# warship_demo_2.net
KiCad netlist of a schematic drawn in Altium Designer
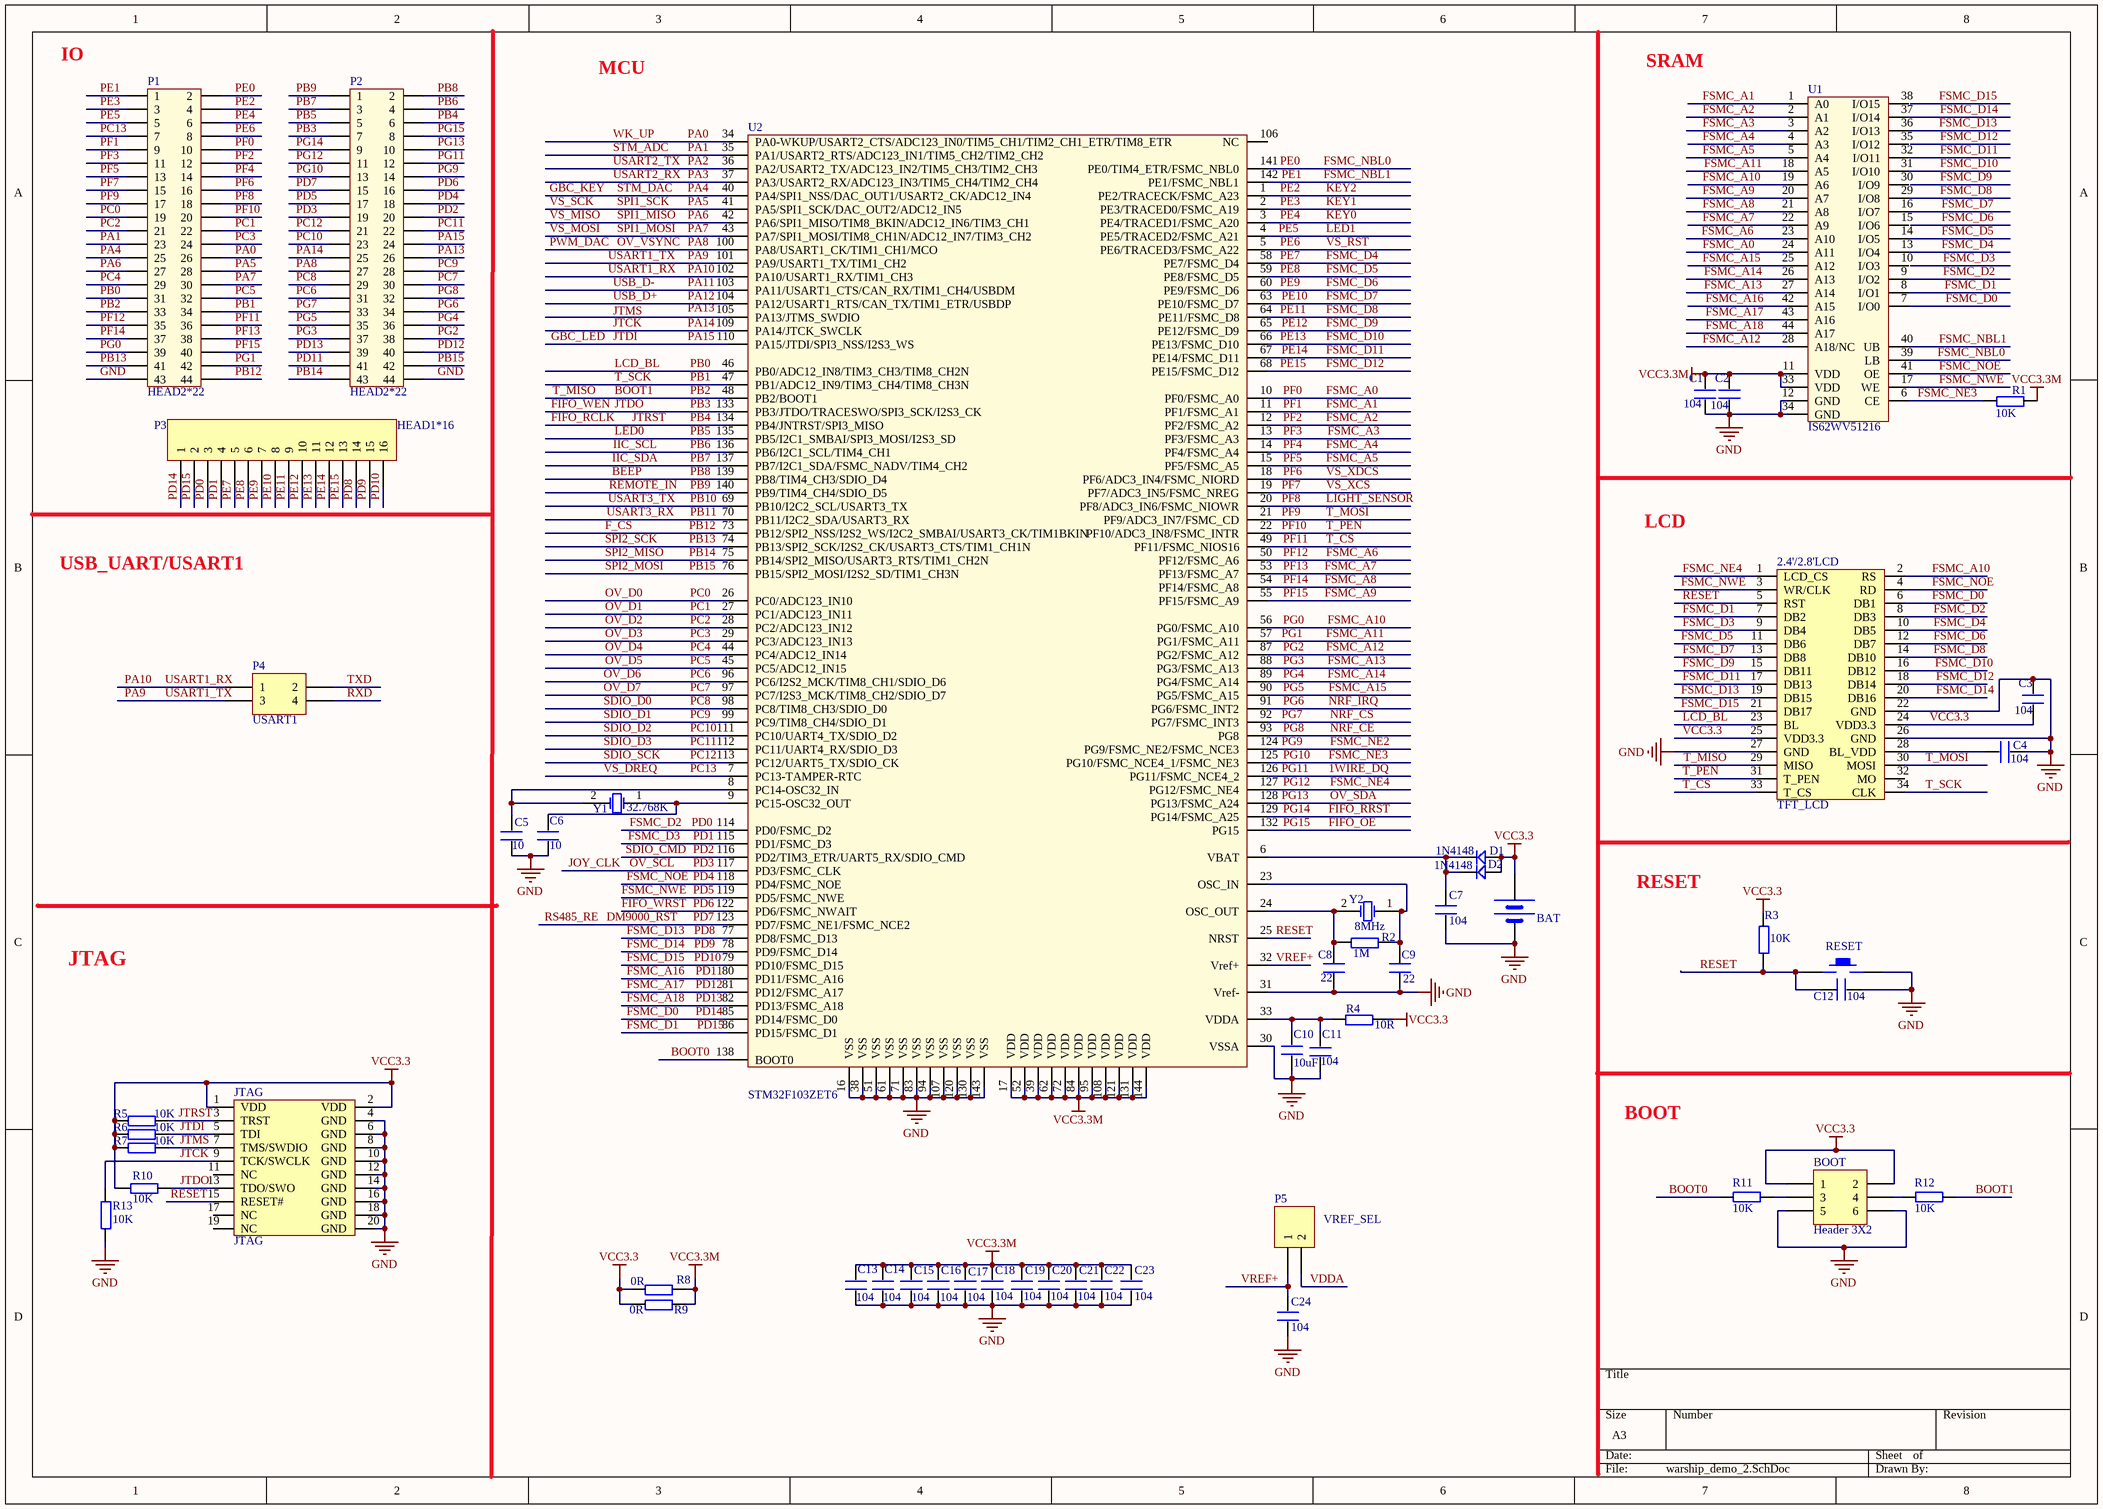
[diagram p0: warship_demo_2.SchDoc]

(export (version "E")
  (design (tool "Eeschema 10.0.6"))
  (components
    (comp (ref "2.4'/2.8'LCD")
      (value "TFT_LCD")
      (footprint "db2*17-4.3")
      (libsource (lib "WarShip V3 STM32103封装库") (part "TFT_LCD"))
    )
    (comp (ref "BAT")
      (value "BATT")
      (footprint "BATM")
      (libsource (lib "WarShip V3 STM32103封装库") (part "BAT"))
    )
    (comp (ref "BOOT")
      (value "Header 3X2")
      (footprint "HDR2X3")
      (description "Header, 3-Pin, Dual row")
      (fields (field (name "PUBLISHER") "Altium Limited"))
      (libsource (lib "WarShip V3 STM32103封装库") (part "Header 3X2"))
    )
    (comp (ref "C1") (value "104") (footprint "0603P") (libsource (lib "WarShip V3 STM32103封装库") (part "C")))
    (comp (ref "C2") (value "104") (footprint "0603P") (libsource (lib "WarShip V3 STM32103封装库") (part "C")))
    (comp (ref "C3") (value "104") (footprint "0603P") (libsource (lib "WarShip V3 STM32103封装库") (part "C")))
    (comp (ref "C4") (value "104") (footprint "0603P") (libsource (lib "WarShip V3 STM32103封装库") (part "C")))
    (comp (ref "C5") (value "10") (footprint "0603P") (libsource (lib "WarShip V3 STM32103封装库") (part "C")))
    (comp (ref "C6") (value "10") (footprint "0603P") (libsource (lib "WarShip V3 STM32103封装库") (part "C")))
    (comp (ref "C7") (value "104") (footprint "0603P") (libsource (lib "WarShip V3 STM32103封装库") (part "C")))
    (comp (ref "C8") (value "22") (footprint "0603P") (libsource (lib "WarShip V3 STM32103封装库") (part "C")))
    (comp (ref "C9") (value "22") (footprint "0603P") (libsource (lib "WarShip V3 STM32103封装库") (part "C")))
    (comp (ref "C10")
      (value "10uF")
      (footprint "0603P")
      (libsource (lib "WarShip V3 STM32103封装库") (part "C"))
    )
    (comp (ref "C11") (value "104") (footprint "0603P") (libsource (lib "WarShip V3 STM32103封装库") (part "C")))
    (comp (ref "C12") (value "104") (footprint "0603P") (libsource (lib "WarShip V3 STM32103封装库") (part "C")))
    (comp (ref "C13") (value "104") (footprint "0603P") (libsource (lib "WarShip V3 STM32103封装库") (part "C")))
    (comp (ref "C14") (value "104") (footprint "0603P") (libsource (lib "WarShip V3 STM32103封装库") (part "C")))
    (comp (ref "C15") (value "104") (footprint "0603P") (libsource (lib "WarShip V3 STM32103封装库") (part "C")))
    (comp (ref "C16") (value "104") (footprint "0603P") (libsource (lib "WarShip V3 STM32103封装库") (part "C")))
    (comp (ref "C17") (value "104") (footprint "0603P") (libsource (lib "WarShip V3 STM32103封装库") (part "C")))
    (comp (ref "C18") (value "104") (footprint "0603P") (libsource (lib "WarShip V3 STM32103封装库") (part "C")))
    (comp (ref "C19") (value "104") (footprint "0603P") (libsource (lib "WarShip V3 STM32103封装库") (part "C")))
    (comp (ref "C20") (value "104") (footprint "0603P") (libsource (lib "WarShip V3 STM32103封装库") (part "C")))
    (comp (ref "C21") (value "104") (footprint "0603P") (libsource (lib "WarShip V3 STM32103封装库") (part "C")))
    (comp (ref "C22") (value "104") (footprint "0603P") (libsource (lib "WarShip V3 STM32103封装库") (part "C")))
    (comp (ref "C23") (value "104") (footprint "0603P") (libsource (lib "WarShip V3 STM32103封装库") (part "C")))
    (comp (ref "C24") (value "104") (footprint "0603P") (libsource (lib "WarShip V3 STM32103封装库") (part "C")))
    (comp (ref "D1")
      (value "1N4148")
      (footprint "DIODE_SOP")
      (libsource (lib "WarShip V3 STM32103封装库") (part "D"))
    )
    (comp (ref "D2")
      (value "1N4148")
      (footprint "DIODE_SOP")
      (libsource (lib "WarShip V3 STM32103封装库") (part "D"))
    )
    (comp (ref "JTAG")
      (value "JTAG")
      (footprint "JTAG_20")
      (libsource (lib "WarShip V3 STM32103封装库") (part "JTAG"))
    )
    (comp (ref "P1")
      (value "HEAD2*22")
      (footprint "HEAD2*22")
      (libsource (lib "WarShip V3 STM32103封装库") (part "HEAD2*22"))
    )
    (comp (ref "P2")
      (value "HEAD2*22")
      (footprint "HEAD2*22")
      (libsource (lib "WarShip V3 STM32103封装库") (part "HEAD2*22"))
    )
    (comp (ref "P3")
      (value "HEAD1*16")
      (footprint "HDR1X16")
      (description "Header, 16-Pin")
      (fields (field (name "PUBLISHER") "Altium Limited"))
      (libsource (lib "WarShip V3 STM32103封装库") (part "Header 16"))
    )
    (comp (ref "P4")
      (value "USART1")
      (footprint "HDR2X2")
      (description "Header, 2-Pin, Dual row")
      (fields (field (name "PUBLISHER") "Altium Limited"))
      (libsource (lib "WarShip V3 STM32103封装库") (part "Header 2X2"))
    )
    (comp (ref "P5")
      (value "VREF_SEL")
      (footprint "HDR1X2")
      (description "Header, 2-Pin")
      (fields (field (name "PUBLISHER") "Altium Limited"))
      (libsource (lib "WarShip V3 STM32103封装库") (part "Header 2"))
    )
    (comp (ref "R1") (value "10K") (footprint "0603P") (libsource (lib "WarShip V3 STM32103封装库") (part "R")))
    (comp (ref "R2") (value "1M") (footprint "0603P") (libsource (lib "WarShip V3 STM32103封装库") (part "R")))
    (comp (ref "R3") (value "10K") (footprint "0603P") (libsource (lib "WarShip V3 STM32103封装库") (part "R")))
    (comp (ref "R4") (value "10R") (footprint "0603P") (libsource (lib "WarShip V3 STM32103封装库") (part "R")))
    (comp (ref "R5") (value "10K") (footprint "0603P") (libsource (lib "WarShip V3 STM32103封装库") (part "R")))
    (comp (ref "R6") (value "10K") (footprint "0603P") (libsource (lib "WarShip V3 STM32103封装库") (part "R")))
    (comp (ref "R7") (value "10K") (footprint "0603P") (libsource (lib "WarShip V3 STM32103封装库") (part "R")))
    (comp (ref "R8") (value "0R") (footprint "0603P") (libsource (lib "WarShip V3 STM32103封装库") (part "R")))
    (comp (ref "R9") (value "0R") (footprint "0603P") (libsource (lib "WarShip V3 STM32103封装库") (part "R")))
    (comp (ref "R10") (value "10K") (footprint "0603P") (libsource (lib "WarShip V3 STM32103封装库") (part "R")))
    (comp (ref "R11") (value "10K") (footprint "0603P") (libsource (lib "WarShip V3 STM32103封装库") (part "R")))
    (comp (ref "R12") (value "10K") (footprint "0603P") (libsource (lib "WarShip V3 STM32103封装库") (part "R")))
    (comp (ref "R13") (value "10K") (footprint "0603P") (libsource (lib "WarShip V3 STM32103封装库") (part "R")))
    (comp (ref "RESET")
      (value "KEY_M")
      (footprint "KEY_M")
      (libsource (lib "WarShip V3 STM32103封装库") (part "KEY_M"))
    )
    (comp (ref "U1")
      (value "IS62WV51216")
      (footprint "TSOP44")
      (libsource (lib "WarShip V3 STM32103封装库") (part "IS61LV51216"))
    )
    (comp (ref "U2")
      (value "STM32F103ZET6")
      (footprint "LQFP144")
      (libsource (lib "WarShip V3 STM32103封装库") (part "STM32F103ZET6"))
    )
    (comp (ref "Y1")
      (value "32.768K")
      (footprint "XTAL_US")
      (description "Crystal Oscillator")
      (fields (field (name "PUBLISHER") "Altium Limited"))
      (libsource (lib "WarShip V3 STM32103封装库") (part "XTAL"))
    )
    (comp (ref "Y2")
      (value "8MHz")
      (footprint "XTAL_US")
      (description "Crystal Oscillator")
      (fields (field (name "PUBLISHER") "Altium Limited"))
      (libsource (lib "WarShip V3 STM32103封装库") (part "XTAL"))
    )
  )
  (nets
    (net (code "1") (name "/1WIRE_DQ") (class "Default")
      (node (ref "P2") (pin "12") (pinfunction "12_12") (pintype "passive"))
      (node (ref "U2") (pin "126") (pinfunction "PG11/FSMC_NCE4_2_126") (pintype "passive"))
    )
    (net (code "2") (name "/BEEP") (class "Default")
      (node (ref "P2") (pin "2") (pinfunction "2_2") (pintype "passive"))
      (node (ref "U2") (pin "139") (pinfunction "PB8/TIM4_CH3/SDIO_D4_139") (pintype "passive"))
    )
    (net (code "3") (name "/BOOT0") (class "Default")
      (node (ref "R11") (pin "2") (pintype "passive"))
      (node (ref "U2") (pin "138") (pinfunction "BOOT0_138") (pintype "passive"))
    )
    (net (code "4") (name "/BOOT1") (class "Default")
      (node (ref "2.4'/2.8'LCD") (pin "29") (pinfunction "MISO_29") (pintype "passive"))
      (node (ref "P1") (pin "33") (pinfunction "33_33") (pintype "passive"))
      (node (ref "R12") (pin "1") (pintype "passive"))
      (node (ref "U2") (pin "48") (pinfunction "PB2/BOOT1_48") (pintype "passive"))
    )
    (net (code "5") (name "/DM9000_RST") (class "Default")
      (node (ref "P2") (pin "15") (pinfunction "15_15") (pintype "passive"))
      (node (ref "U2") (pin "123") (pinfunction "PD7/FSMC_NE1/FSMC_NCE2_123") (pintype "passive"))
    )
    (net (code "6") (name "/FIFO_OE") (class "Default")
      (node (ref "P2") (pin "8") (pinfunction "8_8") (pintype "passive"))
      (node (ref "U2") (pin "132") (pinfunction "PG15_132") (pintype "passive"))
    )
    (net (code "7") (name "/FIFO_RCLK") (class "Default")
      (node (ref "JTAG") (pin "3") (pinfunction "TRST_3") (pintype "passive"))
      (node (ref "P2") (pin "6") (pinfunction "6_6") (pintype "passive"))
      (node (ref "R5") (pin "2") (pintype "passive"))
      (node (ref "U2") (pin "134") (pinfunction "PB4/JNTRST/SPI3_MISO_134") (pintype "passive"))
    )
    (net (code "8") (name "/FIFO_RRST") (class "Default")
      (node (ref "P2") (pin "9") (pinfunction "9_9") (pintype "passive"))
      (node (ref "U2") (pin "129") (pinfunction "PG14/FSMC_A25_129") (pintype "passive"))
    )
    (net (code "9") (name "/FIFO_WEN") (class "Default")
      (node (ref "JTAG") (pin "13") (pinfunction "TDO/SWO_13") (pintype "passive"))
      (node (ref "P2") (pin "7") (pinfunction "7_7") (pintype "passive"))
      (node (ref "R10") (pin "2") (pintype "passive"))
      (node (ref "U2") (pin "133") (pinfunction "PB3/JTDO/TRACESWO/SPI3_SCK/I2S3_CK_133") (pintype "passive"))
    )
    (net (code "10") (name "/FIFO_WRST") (class "Default")
      (node (ref "P2") (pin "16") (pinfunction "16_16") (pintype "passive"))
      (node (ref "U2") (pin "122") (pinfunction "PD6/FSMC_NWAIT_122") (pintype "passive"))
    )
    (net (code "11") (name "/FSMC_A0") (class "Default")
      (node (ref "P1") (pin "10") (pinfunction "10_10") (pintype "passive"))
      (node (ref "U1") (pin "24") (pinfunction "A11_24") (pintype "passive"))
      (node (ref "U2") (pin "10") (pinfunction "PF0/FSMC_A0_10") (pintype "passive"))
    )
    (net (code "12") (name "/FSMC_A1") (class "Default")
      (node (ref "P1") (pin "9") (pinfunction "9_9") (pintype "passive"))
      (node (ref "U1") (pin "1") (pinfunction "A0_1") (pintype "passive"))
      (node (ref "U2") (pin "11") (pinfunction "PF1/FSMC_A1_11") (pintype "passive"))
    )
    (net (code "13") (name "/FSMC_A2") (class "Default")
      (node (ref "P1") (pin "12") (pinfunction "12_12") (pintype "passive"))
      (node (ref "U1") (pin "2") (pinfunction "A1_2") (pintype "passive"))
      (node (ref "U2") (pin "12") (pinfunction "PF2/FSMC_A2_12") (pintype "passive"))
    )
    (net (code "14") (name "/FSMC_A3") (class "Default")
      (node (ref "P1") (pin "11") (pinfunction "11_11") (pintype "passive"))
      (node (ref "U1") (pin "3") (pinfunction "A2_3") (pintype "passive"))
      (node (ref "U2") (pin "13") (pinfunction "PF3/FSMC_A3_13") (pintype "passive"))
    )
    (net (code "15") (name "/FSMC_A4") (class "Default")
      (node (ref "P1") (pin "14") (pinfunction "14_14") (pintype "passive"))
      (node (ref "U1") (pin "4") (pinfunction "A3_4") (pintype "passive"))
      (node (ref "U2") (pin "14") (pinfunction "PF4/FSMC_A4_14") (pintype "passive"))
    )
    (net (code "16") (name "/FSMC_A5") (class "Default")
      (node (ref "P1") (pin "13") (pinfunction "13_13") (pintype "passive"))
      (node (ref "U1") (pin "5") (pinfunction "A4_5") (pintype "passive"))
      (node (ref "U2") (pin "15") (pinfunction "PF5/FSMC_A5_15") (pintype "passive"))
    )
    (net (code "17") (name "/FSMC_A6") (class "Default")
      (node (ref "P1") (pin "35") (pinfunction "35_35") (pintype "passive"))
      (node (ref "U1") (pin "23") (pinfunction "A10_23") (pintype "passive"))
      (node (ref "U2") (pin "50") (pinfunction "PF12/FSMC_A6_50") (pintype "passive"))
    )
    (net (code "18") (name "/FSMC_A7") (class "Default")
      (node (ref "P1") (pin "38") (pinfunction "38_38") (pintype "passive"))
      (node (ref "U1") (pin "22") (pinfunction "A9_22") (pintype "passive"))
      (node (ref "U2") (pin "53") (pinfunction "PF13/FSMC_A7_53") (pintype "passive"))
    )
    (net (code "19") (name "/FSMC_A8") (class "Default")
      (node (ref "P1") (pin "37") (pinfunction "37_37") (pintype "passive"))
      (node (ref "U1") (pin "21") (pinfunction "A8_21") (pintype "passive"))
      (node (ref "U2") (pin "54") (pinfunction "PF14/FSMC_A8_54") (pintype "passive"))
    )
    (net (code "20") (name "/FSMC_A9") (class "Default")
      (node (ref "P1") (pin "40") (pinfunction "40_40") (pintype "passive"))
      (node (ref "U1") (pin "20") (pinfunction "A7_20") (pintype "passive"))
      (node (ref "U2") (pin "55") (pinfunction "PF15/FSMC_A9_55") (pintype "passive"))
    )
    (net (code "21") (name "/FSMC_A10") (class "Default")
      (node (ref "2.4'/2.8'LCD") (pin "2") (pinfunction "RS_2") (pintype "passive"))
      (node (ref "P1") (pin "39") (pinfunction "39_39") (pintype "passive"))
      (node (ref "U1") (pin "19") (pinfunction "A6_19") (pintype "passive"))
      (node (ref "U2") (pin "56") (pinfunction "PG0/FSMC_A10_56") (pintype "passive"))
    )
    (net (code "22") (name "/FSMC_A11") (class "Default")
      (node (ref "P1") (pin "42") (pinfunction "42_42") (pintype "passive"))
      (node (ref "U1") (pin "18") (pinfunction "A5_18") (pintype "passive"))
      (node (ref "U2") (pin "57") (pinfunction "PG1/FSMC_A11_57") (pintype "passive"))
    )
    (net (code "23") (name "/FSMC_A12") (class "Default")
      (node (ref "P2") (pin "38") (pinfunction "38_38") (pintype "passive"))
      (node (ref "U1") (pin "28") (pinfunction "A18/NC_28") (pintype "passive"))
      (node (ref "U2") (pin "87") (pinfunction "PG2/FSMC_A12_87") (pintype "passive"))
    )
    (net (code "24") (name "/FSMC_A13") (class "Default")
      (node (ref "P2") (pin "37") (pinfunction "37_37") (pintype "passive"))
      (node (ref "U1") (pin "27") (pinfunction "A14_27") (pintype "passive"))
      (node (ref "U2") (pin "88") (pinfunction "PG3/FSMC_A13_88") (pintype "passive"))
    )
    (net (code "25") (name "/FSMC_A14") (class "Default")
      (node (ref "P2") (pin "36") (pinfunction "36_36") (pintype "passive"))
      (node (ref "U1") (pin "26") (pinfunction "A13_26") (pintype "passive"))
      (node (ref "U2") (pin "89") (pinfunction "PG4/FSMC_A14_89") (pintype "passive"))
    )
    (net (code "26") (name "/FSMC_A15") (class "Default")
      (node (ref "P2") (pin "35") (pinfunction "35_35") (pintype "passive"))
      (node (ref "U1") (pin "25") (pinfunction "A12_25") (pintype "passive"))
      (node (ref "U2") (pin "90") (pinfunction "PG5/FSMC_A15_90") (pintype "passive"))
    )
    (net (code "27") (name "/FSMC_A16") (class "Default")
      (node (ref "P2") (pin "41") (pinfunction "41_41") (pintype "passive"))
      (node (ref "U1") (pin "42") (pinfunction "A15_42") (pintype "passive"))
      (node (ref "U2") (pin "80") (pinfunction "PD11/FSMC_A16_80") (pintype "passive"))
    )
    (net (code "28") (name "/FSMC_A17") (class "Default")
      (node (ref "P2") (pin "40") (pinfunction "40_40") (pintype "passive"))
      (node (ref "U1") (pin "43") (pinfunction "A16_43") (pintype "passive"))
      (node (ref "U2") (pin "81") (pinfunction "PD12/FSMC_A17_81") (pintype "passive"))
    )
    (net (code "29") (name "/FSMC_A18") (class "Default")
      (node (ref "P2") (pin "39") (pinfunction "39_39") (pintype "passive"))
      (node (ref "U1") (pin "44") (pinfunction "A17_44") (pintype "passive"))
      (node (ref "U2") (pin "82") (pinfunction "PD13/FSMC_A18_82") (pintype "passive"))
    )
    (net (code "30") (name "/FSMC_D0") (class "Default")
      (node (ref "2.4'/2.8'LCD") (pin "6") (pinfunction "DB1_6") (pintype "passive"))
      (node (ref "P3") (pin "1") (pinfunction "1_1") (pintype "passive"))
      (node (ref "U1") (pin "7") (pinfunction "I/O0_7") (pintype "passive"))
      (node (ref "U2") (pin "85") (pinfunction "PD14/FSMC_D0_85") (pintype "passive"))
    )
    (net (code "31") (name "/FSMC_D1") (class "Default")
      (node (ref "2.4'/2.8'LCD") (pin "7") (pinfunction "DB2_7") (pintype "passive"))
      (node (ref "P3") (pin "2") (pinfunction "2_2") (pintype "passive"))
      (node (ref "U1") (pin "8") (pinfunction "I/O1_8") (pintype "passive"))
      (node (ref "U2") (pin "86") (pinfunction "PD15/FSMC_D1_86") (pintype "passive"))
    )
    (net (code "32") (name "/FSMC_D2") (class "Default")
      (node (ref "2.4'/2.8'LCD") (pin "8") (pinfunction "DB3_8") (pintype "passive"))
      (node (ref "P3") (pin "3") (pinfunction "3_3") (pintype "passive"))
      (node (ref "U1") (pin "9") (pinfunction "I/O2_9") (pintype "passive"))
      (node (ref "U2") (pin "114") (pinfunction "PD0/FSMC_D2_114") (pintype "passive"))
    )
    (net (code "33") (name "/FSMC_D3") (class "Default")
      (node (ref "2.4'/2.8'LCD") (pin "9") (pinfunction "DB4_9") (pintype "passive"))
      (node (ref "P3") (pin "4") (pinfunction "4_4") (pintype "passive"))
      (node (ref "U2") (pin "115") (pinfunction "PD1/FSMC_D3_115") (pintype "passive"))
    )
    (net (code "34") (name "/FSMC_D4") (class "Default")
      (node (ref "2.4'/2.8'LCD") (pin "10") (pinfunction "DB5_10") (pintype "passive"))
      (node (ref "P3") (pin "5") (pinfunction "5_5") (pintype "passive"))
      (node (ref "U1") (pin "13") (pinfunction "I/O4_13") (pintype "passive"))
      (node (ref "U2") (pin "58") (pinfunction "PE7/FSMC_D4_58") (pintype "passive"))
    )
    (net (code "35") (name "/FSMC_D5") (class "Default")
      (node (ref "2.4'/2.8'LCD") (pin "11") (pinfunction "DB6_11") (pintype "passive"))
      (node (ref "P3") (pin "6") (pinfunction "6_6") (pintype "passive"))
      (node (ref "U1") (pin "14") (pinfunction "I/O5_14") (pintype "passive"))
      (node (ref "U2") (pin "59") (pinfunction "PE8/FSMC_D5_59") (pintype "passive"))
    )
    (net (code "36") (name "/FSMC_D6") (class "Default")
      (node (ref "2.4'/2.8'LCD") (pin "12") (pinfunction "DB7_12") (pintype "passive"))
      (node (ref "P3") (pin "7") (pinfunction "7_7") (pintype "passive"))
      (node (ref "U2") (pin "60") (pinfunction "PE9/FSMC_D6_60") (pintype "passive"))
    )
    (net (code "37") (name "/FSMC_D7") (class "Default")
      (node (ref "2.4'/2.8'LCD") (pin "13") (pinfunction "DB8_13") (pintype "passive"))
      (node (ref "P3") (pin "8") (pinfunction "8_8") (pintype "passive"))
      (node (ref "U1") (pin "16") (pinfunction "I/O7_16") (pintype "passive"))
      (node (ref "U2") (pin "63") (pinfunction "PE10/FSMC_D7_63") (pintype "passive"))
    )
    (net (code "38") (name "/FSMC_D8") (class "Default")
      (node (ref "2.4'/2.8'LCD") (pin "14") (pinfunction "DB10_14") (pintype "passive"))
      (node (ref "P3") (pin "9") (pinfunction "9_9") (pintype "passive"))
      (node (ref "U1") (pin "29") (pinfunction "I/O8_29") (pintype "passive"))
      (node (ref "U2") (pin "64") (pinfunction "PE11/FSMC_D8_64") (pintype "passive"))
    )
    (net (code "39") (name "/FSMC_D9") (class "Default")
      (node (ref "2.4'/2.8'LCD") (pin "15") (pinfunction "DB11_15") (pintype "passive"))
      (node (ref "P3") (pin "10") (pinfunction "10_10") (pintype "passive"))
      (node (ref "U2") (pin "65") (pinfunction "PE12/FSMC_D9_65") (pintype "passive"))
    )
    (net (code "40") (name "/FSMC_D10") (class "Default")
      (node (ref "2.4'/2.8'LCD") (pin "16") (pinfunction "DB12_16") (pintype "passive"))
      (node (ref "P3") (pin "11") (pinfunction "11_11") (pintype "passive"))
      (node (ref "U1") (pin "31") (pinfunction "I/O10_31") (pintype "passive"))
      (node (ref "U2") (pin "66") (pinfunction "PE13/FSMC_D10_66") (pintype "passive"))
    )
    (net (code "41") (name "/FSMC_D11") (class "Default")
      (node (ref "2.4'/2.8'LCD") (pin "17") (pinfunction "DB13_17") (pintype "passive"))
      (node (ref "P3") (pin "12") (pinfunction "12_12") (pintype "passive"))
      (node (ref "U1") (pin "32") (pinfunction "I/O11_32") (pintype "passive"))
      (node (ref "U2") (pin "67") (pinfunction "PE14/FSMC_D11_67") (pintype "passive"))
    )
    (net (code "42") (name "/FSMC_D12") (class "Default")
      (node (ref "2.4'/2.8'LCD") (pin "18") (pinfunction "DB14_18") (pintype "passive"))
      (node (ref "P3") (pin "13") (pinfunction "13_13") (pintype "passive"))
      (node (ref "U2") (pin "68") (pinfunction "PE15/FSMC_D12_68") (pintype "passive"))
    )
    (net (code "43") (name "/FSMC_D13") (class "Default")
      (node (ref "2.4'/2.8'LCD") (pin "19") (pinfunction "DB15_19") (pintype "passive"))
      (node (ref "P3") (pin "14") (pinfunction "14_14") (pintype "passive"))
      (node (ref "U1") (pin "36") (pinfunction "I/O13_36") (pintype "passive"))
      (node (ref "U2") (pin "77") (pinfunction "PD8/FSMC_D13_77") (pintype "passive"))
    )
    (net (code "44") (name "/FSMC_D14") (class "Default")
      (node (ref "2.4'/2.8'LCD") (pin "20") (pinfunction "DB16_20") (pintype "passive"))
      (node (ref "P3") (pin "15") (pinfunction "15_15") (pintype "passive"))
      (node (ref "U1") (pin "37") (pinfunction "I/O14_37") (pintype "passive"))
      (node (ref "U2") (pin "78") (pinfunction "PD9/FSMC_D14_78") (pintype "passive"))
    )
    (net (code "45") (name "/FSMC_D15") (class "Default")
      (node (ref "2.4'/2.8'LCD") (pin "21") (pinfunction "DB17_21") (pintype "passive"))
      (node (ref "P3") (pin "16") (pinfunction "16_16") (pintype "passive"))
      (node (ref "U2") (pin "79") (pinfunction "PD10/FSMC_D15_79") (pintype "passive"))
    )
    (net (code "46") (name "/FSMC_NBL0") (class "Default")
      (node (ref "P1") (pin "2") (pinfunction "2_2") (pintype "passive"))
      (node (ref "U1") (pin "39") (pinfunction "LB_39") (pintype "passive"))
      (node (ref "U2") (pin "141") (pinfunction "PE0/TIM4_ETR/FSMC_NBL0_141") (pintype "passive"))
    )
    (net (code "47") (name "/FSMC_NBL1") (class "Default")
      (node (ref "P1") (pin "1") (pinfunction "1_1") (pintype "passive"))
      (node (ref "U1") (pin "40") (pinfunction "UB_40") (pintype "passive"))
      (node (ref "U2") (pin "142") (pinfunction "PE1/FSMC_NBL1_142") (pintype "passive"))
    )
    (net (code "48") (name "/FSMC_NE2") (class "Default")
      (node (ref "P2") (pin "14") (pinfunction "14_14") (pintype "passive"))
      (node (ref "U2") (pin "124") (pinfunction "PG9/FSMC_NE2/FSMC_NCE3_124") (pintype "passive"))
    )
    (net (code "49") (name "/FSMC_NE3") (class "Default")
      (node (ref "P2") (pin "13") (pinfunction "13_13") (pintype "passive"))
      (node (ref "R1") (pin "1") (pintype "passive"))
      (node (ref "U1") (pin "6") (pinfunction "CE_6") (pintype "passive"))
      (node (ref "U2") (pin "125") (pinfunction "PG10/FSMC_NCE4_1/FSMC_NE3_125") (pintype "passive"))
    )
    (net (code "50") (name "/FSMC_NE4") (class "Default")
      (node (ref "2.4'/2.8'LCD") (pin "1") (pinfunction "LCD_CS_1") (pintype "passive"))
      (node (ref "P2") (pin "11") (pinfunction "11_11") (pintype "passive"))
      (node (ref "U2") (pin "127") (pinfunction "PG12/FSMC_NE4_127") (pintype "passive"))
    )
    (net (code "51") (name "/FSMC_NOE") (class "Default")
      (node (ref "2.4'/2.8'LCD") (pin "4") (pinfunction "RD_4") (pintype "passive"))
      (node (ref "P2") (pin "18") (pinfunction "18_18") (pintype "passive"))
      (node (ref "U1") (pin "41") (pinfunction "OE_41") (pintype "passive"))
      (node (ref "U2") (pin "118") (pinfunction "PD4/FSMC_NOE_118") (pintype "passive"))
    )
    (net (code "52") (name "/FSMC_NWE") (class "Default")
      (node (ref "2.4'/2.8'LCD") (pin "3") (pinfunction "WR/CLK_3") (pintype "passive"))
      (node (ref "P2") (pin "17") (pinfunction "17_17") (pintype "passive"))
      (node (ref "U1") (pin "17") (pinfunction "WE_17") (pintype "passive"))
      (node (ref "U2") (pin "119") (pinfunction "PD5/FSMC_NWE_119") (pintype "passive"))
    )
    (net (code "53") (name "/F_CS") (class "Default")
      (node (ref "P1") (pin "44") (pinfunction "44_44") (pintype "passive"))
      (node (ref "U2") (pin "73") (pinfunction "PB12/SPI2_NSS/I2S2_WS/I2C2_SMBAI/USART3_CK/TIM1BKIN_73") (pintype "passive"))
    )
    (net (code "54") (name "/GBC_KEY") (class "Default")
      (node (ref "P1") (pin "25") (pinfunction "25_25") (pintype "passive"))
      (node (ref "U2") (pin "40") (pinfunction "PA4/SPI1_NSS/DAC_OUT1/USART2_CK/ADC12_IN4_40") (pintype "passive"))
    )
    (net (code "55") (name "/GBC_LED") (class "Default")
      (node (ref "JTAG") (pin "5") (pinfunction "TDI_5") (pintype "passive"))
      (node (ref "P2") (pin "24") (pinfunction "24_24") (pintype "passive"))
      (node (ref "R6") (pin "2") (pintype "passive"))
      (node (ref "U2") (pin "110") (pinfunction "PA15/JTDI/SPI3_NSS/I2S3_WS_110") (pintype "passive"))
    )
    (net (code "56") (name "/IIC_SCL") (class "Default")
      (node (ref "P2") (pin "4") (pinfunction "4_4") (pintype "passive"))
      (node (ref "U2") (pin "136") (pinfunction "PB6/I2C1_SCL/TIM4_CH1_136") (pintype "passive"))
    )
    (net (code "57") (name "/IIC_SDA") (class "Default")
      (node (ref "P2") (pin "3") (pinfunction "3_3") (pintype "passive"))
      (node (ref "U2") (pin "137") (pinfunction "PB7/I2C1_SDA/FSMC_NADV/TIM4_CH2_137") (pintype "passive"))
    )
    (net (code "58") (name "/JOY_CLK") (class "Default")
      (node (ref "P2") (pin "19") (pinfunction "19_19") (pintype "passive"))
      (node (ref "U2") (pin "117") (pinfunction "PD3/FSMC_CLK_117") (pintype "passive"))
    )
    (net (code "59") (name "/JTCK") (class "Default")
      (node (ref "JTAG") (pin "9") (pinfunction "TCK/SWCLK_9") (pintype "passive"))
      (node (ref "P2") (pin "25") (pinfunction "25_25") (pintype "passive"))
      (node (ref "R13") (pin "2") (pintype "passive"))
      (node (ref "U2") (pin "109") (pinfunction "PA14/JTCK_SWCLK_109") (pintype "passive"))
    )
    (net (code "60") (name "/JTMS") (class "Default")
      (node (ref "JTAG") (pin "7") (pinfunction "TMS/SWDIO_7") (pintype "passive"))
      (node (ref "R7") (pin "2") (pintype "passive"))
    )
    (net (code "61") (name "/KEY0") (class "Default")
      (node (ref "P1") (pin "6") (pinfunction "6_6") (pintype "passive"))
      (node (ref "U2") (pin "3") (pinfunction "PE4/TRACED1/FSMC_A20_3") (pintype "passive"))
    )
    (net (code "62") (name "/KEY1") (class "Default")
      (node (ref "P1") (pin "3") (pinfunction "3_3") (pintype "passive"))
      (node (ref "U2") (pin "2") (pinfunction "PE3/TRACED0/FSMC_A19_2") (pintype "passive"))
    )
    (net (code "63") (name "/KEY2") (class "Default")
      (node (ref "P1") (pin "4") (pinfunction "4_4") (pintype "passive"))
      (node (ref "U2") (pin "1") (pinfunction "PE2/TRACECK/FSMC_A23_1") (pintype "passive"))
    )
    (net (code "64") (name "/LCD_BL") (class "Default")
      (node (ref "2.4'/2.8'LCD") (pin "23") (pinfunction "BL_23") (pintype "passive"))
      (node (ref "P1") (pin "31") (pinfunction "31_31") (pintype "passive"))
      (node (ref "U2") (pin "46") (pinfunction "PB0/ADC12_IN8/TIM3_CH3/TIM8_CH2N_46") (pintype "passive"))
    )
    (net (code "65") (name "/LED0") (class "Default")
      (node (ref "P2") (pin "5") (pinfunction "5_5") (pintype "passive"))
      (node (ref "U2") (pin "135") (pinfunction "PB5/I2C1_SMBAI/SPI3_MOSI/I2S3_SD_135") (pintype "passive"))
    )
    (net (code "66") (name "/LED1") (class "Default")
      (node (ref "P1") (pin "5") (pinfunction "5_5") (pintype "passive"))
      (node (ref "U2") (pin "4") (pinfunction "PE5/TRACED2/FSMC_A21_4") (pintype "passive"))
    )
    (net (code "67") (name "/LIGHT_SENSOR") (class "Default")
      (node (ref "P1") (pin "18") (pinfunction "18_18") (pintype "passive"))
      (node (ref "U2") (pin "20") (pinfunction "PF8/ADC3_IN6/FSMC_NIOWR_20") (pintype "passive"))
    )
    (net (code "68") (name "/NRF_CE") (class "Default")
      (node (ref "P2") (pin "32") (pinfunction "32_32") (pintype "passive"))
      (node (ref "U2") (pin "93") (pinfunction "PG8_93") (pintype "passive"))
    )
    (net (code "69") (name "/NRF_CS") (class "Default")
      (node (ref "P2") (pin "33") (pinfunction "33_33") (pintype "passive"))
      (node (ref "U2") (pin "92") (pinfunction "PG7/FSMC_INT3_92") (pintype "passive"))
    )
    (net (code "70") (name "/NRF_IRQ") (class "Default")
      (node (ref "P2") (pin "34") (pinfunction "34_34") (pintype "passive"))
      (node (ref "U2") (pin "91") (pinfunction "PG6/FSMC_INT2_91") (pintype "passive"))
    )
    (net (code "71") (name "/OV_D0") (class "Default")
      (node (ref "P1") (pin "19") (pinfunction "19_19") (pintype "passive"))
      (node (ref "U2") (pin "26") (pinfunction "PC0/ADC123_IN10_26") (pintype "passive"))
    )
    (net (code "72") (name "/OV_D1") (class "Default")
      (node (ref "P1") (pin "22") (pinfunction "22_22") (pintype "passive"))
      (node (ref "U2") (pin "27") (pinfunction "PC1/ADC123_IN11_27") (pintype "passive"))
    )
    (net (code "73") (name "/OV_D2") (class "Default")
      (node (ref "P1") (pin "21") (pinfunction "21_21") (pintype "passive"))
      (node (ref "U2") (pin "28") (pinfunction "PC2/ADC123_IN12_28") (pintype "passive"))
    )
    (net (code "74") (name "/OV_D3") (class "Default")
      (node (ref "P1") (pin "24") (pinfunction "24_24") (pintype "passive"))
      (node (ref "U2") (pin "29") (pinfunction "PC3/ADC123_IN13_29") (pintype "passive"))
    )
    (net (code "75") (name "/OV_D4") (class "Default")
      (node (ref "P1") (pin "29") (pinfunction "29_29") (pintype "passive"))
      (node (ref "U2") (pin "44") (pinfunction "PC4/ADC12_IN14_44") (pintype "passive"))
    )
    (net (code "76") (name "/OV_D5") (class "Default")
      (node (ref "P1") (pin "32") (pinfunction "32_32") (pintype "passive"))
      (node (ref "U2") (pin "45") (pinfunction "PC5/ADC12_IN15_45") (pintype "passive"))
    )
    (net (code "77") (name "/OV_D6") (class "Default")
      (node (ref "P2") (pin "31") (pinfunction "31_31") (pintype "passive"))
      (node (ref "U2") (pin "96") (pinfunction "PC6/I2S2_MCK/TIM8_CH1/SDIO_D6_96") (pintype "passive"))
    )
    (net (code "78") (name "/OV_D7") (class "Default")
      (node (ref "P2") (pin "30") (pinfunction "30_30") (pintype "passive"))
      (node (ref "U2") (pin "97") (pinfunction "PC7/I2S3_MCK/TIM8_CH2/SDIO_D7_97") (pintype "passive"))
    )
    (net (code "79") (name "/OV_SDA") (class "Default")
      (node (ref "P2") (pin "10") (pinfunction "10_10") (pintype "passive"))
      (node (ref "U2") (pin "128") (pinfunction "PG13/FSMC_A24_128") (pintype "passive"))
    )
    (net (code "80") (name "/OV_VSYNC") (class "Default")
      (node (ref "P2") (pin "27") (pinfunction "27_27") (pintype "passive"))
      (node (ref "U2") (pin "100") (pinfunction "PA8/USART1_CK/TIM1_CH1/MCO_100") (pintype "passive"))
    )
    (net (code "81") (name "/PA0") (class "Default")
      (node (ref "P1") (pin "26") (pinfunction "26_26") (pintype "passive"))
      (node (ref "U2") (pin "34") (pinfunction "PA0-WKUP/USART2_CTS/ADC123_IN0/TIM5_CH1/TIM2_CH1_ETR/TIM8_ETR_34") (pintype "passive"))
    )
    (net (code "82") (name "/PA1") (class "Default")
      (node (ref "P1") (pin "23") (pinfunction "23_23") (pintype "passive"))
      (node (ref "U2") (pin "35") (pinfunction "PA1/USART2_RTS/ADC123_IN1/TIM5_CH2/TIM2_CH2_35") (pintype "passive"))
    )
    (net (code "83") (name "/PA2") (class "Default")
      (node (ref "U2") (pin "36") (pinfunction "PA2/USART2_TX/ADC123_IN2/TIM5_CH3/TIM2_CH3_36") (pintype "passive"))
    )
    (net (code "84") (name "/PA3") (class "Default")
      (node (ref "U2") (pin "37") (pinfunction "PA3/USART2_RX/ADC123_IN3/TIM5_CH4/TIM2_CH4_37") (pintype "passive"))
    )
    (net (code "85") (name "/PA5") (class "Default")
      (node (ref "P1") (pin "28") (pinfunction "28_28") (pintype "passive"))
      (node (ref "U2") (pin "41") (pinfunction "PA5/SPI1_SCK/DAC_OUT2/ADC12_IN5_41") (pintype "passive"))
    )
    (net (code "86") (name "/PA6") (class "Default")
      (node (ref "P1") (pin "27") (pinfunction "27_27") (pintype "passive"))
      (node (ref "U2") (pin "42") (pinfunction "PA6/SPI1_MISO/TIM8_BKIN/ADC12_IN6/TIM3_CH1_42") (pintype "passive"))
    )
    (net (code "87") (name "/PA7") (class "Default")
      (node (ref "P1") (pin "30") (pinfunction "30_30") (pintype "passive"))
      (node (ref "U2") (pin "43") (pinfunction "PA7/SPI1_MOSI/TIM8_CH1N/ADC12_IN7/TIM3_CH2_43") (pintype "passive"))
    )
    (net (code "88") (name "/PA9") (class "Default")
      (node (ref "P4") (pin "3") (pinfunction "3_3") (pintype "passive"))
      (node (ref "U2") (pin "101") (pinfunction "PA9/USART1_TX/TIM1_CH2_101") (pintype "passive"))
    )
    (net (code "89") (name "/PA10") (class "Default")
      (node (ref "P4") (pin "1") (pinfunction "1_1") (pintype "passive"))
      (node (ref "U2") (pin "102") (pinfunction "PA10/USART1_RX/TIM1_CH3_102") (pintype "passive"))
    )
    (net (code "90") (name "/PA11") (class "Default")
      (node (ref "U2") (pin "103") (pinfunction "PA11/USART1_CTS/CAN_RX/TIM1_CH4/USBDM_103") (pintype "passive"))
    )
    (net (code "91") (name "/PA12") (class "Default")
      (node (ref "U2") (pin "104") (pinfunction "PA12/USART1_RTS/CAN_TX/TIM1_ETR/USBDP_104") (pintype "passive"))
    )
    (net (code "92") (name "/PA13") (class "Default")
      (node (ref "P2") (pin "26") (pinfunction "26_26") (pintype "passive"))
    )
    (net (code "93") (name "/PB1") (class "Default")
      (node (ref "2.4'/2.8'LCD") (pin "34") (pinfunction "CLK_34") (pintype "passive"))
      (node (ref "P1") (pin "34") (pinfunction "34_34") (pintype "passive"))
      (node (ref "U2") (pin "47") (pinfunction "PB1/ADC12_IN9/TIM3_CH4/TIM8_CH3N_47") (pintype "passive"))
    )
    (net (code "94") (name "/PB9") (class "Default")
      (node (ref "P2") (pin "1") (pinfunction "1_1") (pintype "passive"))
      (node (ref "U2") (pin "140") (pinfunction "PB9/TIM4_CH4/SDIO_D5_140") (pintype "passive"))
    )
    (net (code "95") (name "/PB10") (class "Default")
      (node (ref "U2") (pin "69") (pinfunction "PB10/I2C2_SCL/USART3_TX_69") (pintype "passive"))
    )
    (net (code "96") (name "/PB11") (class "Default")
      (node (ref "U2") (pin "70") (pinfunction "PB11/I2C2_SDA/USART3_RX_70") (pintype "passive"))
    )
    (net (code "97") (name "/PB13") (class "Default")
      (node (ref "P1") (pin "41") (pinfunction "41_41") (pintype "passive"))
      (node (ref "U2") (pin "74") (pinfunction "PB13/SPI2_SCK/I2S2_CK/USART3_CTS/TIM1_CH1N_74") (pintype "passive"))
    )
    (net (code "98") (name "/PB14") (class "Default")
      (node (ref "P2") (pin "43") (pinfunction "43_43") (pintype "passive"))
      (node (ref "U2") (pin "75") (pinfunction "PB14/SPI2_MISO/USART3_RTS/TIM1_CH2N_75") (pintype "passive"))
    )
    (net (code "99") (name "/PB15") (class "Default")
      (node (ref "P2") (pin "42") (pinfunction "42_42") (pintype "passive"))
      (node (ref "U2") (pin "76") (pinfunction "PB15/SPI2_MOSI/I2S2_SD/TIM1_CH3N_76") (pintype "passive"))
    )
    (net (code "100") (name "/PC8") (class "Default")
      (node (ref "P2") (pin "29") (pinfunction "29_29") (pintype "passive"))
      (node (ref "U2") (pin "98") (pinfunction "PC8/TIM8_CH3/SDIO_D0_98") (pintype "passive"))
    )
    (net (code "101") (name "/PC9") (class "Default")
      (node (ref "P2") (pin "28") (pinfunction "28_28") (pintype "passive"))
      (node (ref "U2") (pin "99") (pinfunction "PC9/TIM8_CH4/SDIO_D1_99") (pintype "passive"))
    )
    (net (code "102") (name "/PC10") (class "Default")
      (node (ref "P2") (pin "23") (pinfunction "23_23") (pintype "passive"))
      (node (ref "U2") (pin "111") (pinfunction "PC10/UART4_TX/SDIO_D2_111") (pintype "passive"))
    )
    (net (code "103") (name "/PC11") (class "Default")
      (node (ref "P2") (pin "22") (pinfunction "22_22") (pintype "passive"))
      (node (ref "U2") (pin "112") (pinfunction "PC11/UART4_RX/SDIO_D3_112") (pintype "passive"))
    )
    (net (code "104") (name "/PC12") (class "Default")
      (node (ref "P2") (pin "21") (pinfunction "21_21") (pintype "passive"))
      (node (ref "U2") (pin "113") (pinfunction "PC12/UART5_TX/SDIO_CK_113") (pintype "passive"))
    )
    (net (code "105") (name "/PC13") (class "Default")
      (node (ref "P1") (pin "7") (pinfunction "7_7") (pintype "passive"))
      (node (ref "U2") (pin "7") (pinfunction "PC13-TAMPER-RTC_7") (pintype "passive"))
    )
    (net (code "106") (name "/PD2") (class "Default")
      (node (ref "P2") (pin "20") (pinfunction "20_20") (pintype "passive"))
      (node (ref "U2") (pin "116") (pinfunction "PD2/TIM3_ETR/UART5_RX/SDIO_CMD_116") (pintype "passive"))
    )
    (net (code "107") (name "/PE6") (class "Default")
      (node (ref "P1") (pin "8") (pinfunction "8_8") (pintype "passive"))
      (node (ref "U2") (pin "5") (pinfunction "PE6/TRACED3/FSMC_A22_5") (pintype "passive"))
    )
    (net (code "108") (name "/PF6") (class "Default")
      (node (ref "P1") (pin "16") (pinfunction "16_16") (pintype "passive"))
      (node (ref "U2") (pin "18") (pinfunction "PF6/ADC3_IN4/FSMC_NIORD_18") (pintype "passive"))
    )
    (net (code "109") (name "/PF7") (class "Default")
      (node (ref "P1") (pin "15") (pinfunction "15_15") (pintype "passive"))
      (node (ref "U2") (pin "19") (pinfunction "PF7/ADC3_IN5/FSMC_NREG_19") (pintype "passive"))
    )
    (net (code "110") (name "/PF9") (class "Default")
      (node (ref "2.4'/2.8'LCD") (pin "30") (pinfunction "MOSI_30") (pintype "passive"))
      (node (ref "P1") (pin "17") (pinfunction "17_17") (pintype "passive"))
      (node (ref "U2") (pin "21") (pinfunction "PF9/ADC3_IN7/FSMC_CD_21") (pintype "passive"))
    )
    (net (code "111") (name "/PF10") (class "Default")
      (node (ref "2.4'/2.8'LCD") (pin "31") (pinfunction "T_PEN_31") (pintype "passive"))
      (node (ref "P1") (pin "20") (pinfunction "20_20") (pintype "passive"))
      (node (ref "U2") (pin "22") (pinfunction "PF10/ADC3_IN8/FSMC_INTR_22") (pintype "passive"))
    )
    (net (code "112") (name "/PF11") (class "Default")
      (node (ref "2.4'/2.8'LCD") (pin "33") (pinfunction "T_CS_33") (pintype "passive"))
      (node (ref "P1") (pin "36") (pinfunction "36_36") (pintype "passive"))
      (node (ref "U2") (pin "49") (pinfunction "PF11/FSMC_NIOS16_49") (pintype "passive"))
    )
    (net (code "113") (name "/RESET") (class "Default")
      (node (ref "2.4'/2.8'LCD") (pin "5") (pinfunction "RST_5") (pintype "passive"))
      (node (ref "C12") (pin "1") (pintype "passive"))
      (node (ref "JTAG") (pin "15") (pinfunction "RESET#_15") (pintype "passive"))
      (node (ref "R3") (pin "1") (pintype "passive"))
      (node (ref "RESET") (pin "1") (pinfunction "1_1") (pintype "passive"))
      (node (ref "U2") (pin "25") (pinfunction "NRST_25") (pintype "passive"))
    )
    (net (code "114") (name "/RXD") (class "Default")
      (node (ref "P4") (pin "4") (pinfunction "4_4") (pintype "passive"))
    )
    (net (code "115") (name "/TXD") (class "Default")
      (node (ref "P4") (pin "2") (pinfunction "2_2") (pintype "passive"))
    )
    (net (code "116") (name "/VDDA") (class "Default")
      (node (ref "P5") (pin "2") (pinfunction "2_2") (pintype "passive"))
    )
    (net (code "117") (name "/VREF+") (class "Default")
      (node (ref "C24") (pin "2") (pintype "passive"))
      (node (ref "P5") (pin "1") (pinfunction "1_1") (pintype "passive"))
      (node (ref "U2") (pin "32") (pinfunction "Vref+_32") (pintype "passive"))
    )
    (net (code "118") (name "GND") (class "Default")
      (node (ref "2.4'/2.8'LCD") (pin "22") (pinfunction "GND_22") (pintype "passive"))
      (node (ref "2.4'/2.8'LCD") (pin "26") (pinfunction "GND_26") (pintype "passive"))
      (node (ref "2.4'/2.8'LCD") (pin "27") (pinfunction "GND_27") (pintype "passive"))
      (node (ref "BAT") (pin "2") (pinfunction "GND_2") (pintype "passive"))
      (node (ref "BOOT") (pin "5") (pinfunction "5_5") (pintype "passive"))
      (node (ref "BOOT") (pin "6") (pinfunction "6_6") (pintype "passive"))
      (node (ref "C1") (pin "1") (pintype "passive"))
      (node (ref "C10") (pin "1") (pintype "passive"))
      (node (ref "C11") (pin "2") (pintype "passive"))
      (node (ref "C12") (pin "2") (pintype "passive"))
      (node (ref "C13") (pin "1") (pintype "passive"))
      (node (ref "C14") (pin "1") (pintype "passive"))
      (node (ref "C15") (pin "1") (pintype "passive"))
      (node (ref "C16") (pin "1") (pintype "passive"))
      (node (ref "C17") (pin "1") (pintype "passive"))
      (node (ref "C18") (pin "1") (pintype "passive"))
      (node (ref "C19") (pin "1") (pintype "passive"))
      (node (ref "C2") (pin "2") (pintype "passive"))
      (node (ref "C20") (pin "1") (pintype "passive"))
      (node (ref "C21") (pin "1") (pintype "passive"))
      (node (ref "C22") (pin "1") (pintype "passive"))
      (node (ref "C23") (pin "1") (pintype "passive"))
      (node (ref "C24") (pin "1") (pintype "passive"))
      (node (ref "C3") (pin "1") (pintype "passive"))
      (node (ref "C4") (pin "2") (pintype "passive"))
      (node (ref "C5") (pin "1") (pintype "passive"))
      (node (ref "C6") (pin "1") (pintype "passive"))
      (node (ref "C7") (pin "1") (pintype "passive"))
      (node (ref "C8") (pin "1") (pintype "passive"))
      (node (ref "C9") (pin "2") (pintype "passive"))
      (node (ref "JTAG") (pin "10") (pinfunction "GND_10") (pintype "passive"))
      (node (ref "JTAG") (pin "12") (pinfunction "GND_12") (pintype "passive"))
      (node (ref "JTAG") (pin "14") (pinfunction "GND_14") (pintype "passive"))
      (node (ref "JTAG") (pin "16") (pinfunction "GND_16") (pintype "passive"))
      (node (ref "JTAG") (pin "18") (pinfunction "GND_18") (pintype "passive"))
      (node (ref "JTAG") (pin "20") (pinfunction "GND_20") (pintype "passive"))
      (node (ref "JTAG") (pin "4") (pinfunction "GND_4") (pintype "passive"))
      (node (ref "JTAG") (pin "6") (pinfunction "GND_6") (pintype "passive"))
      (node (ref "JTAG") (pin "8") (pinfunction "GND_8") (pintype "passive"))
      (node (ref "P1") (pin "43") (pinfunction "43_43") (pintype "passive"))
      (node (ref "P2") (pin "44") (pinfunction "44_44") (pintype "passive"))
      (node (ref "R13") (pin "1") (pintype "passive"))
      (node (ref "RESET") (pin "2") (pinfunction "2_2") (pintype "passive"))
      (node (ref "U1") (pin "12") (pinfunction "GND_12") (pintype "passive"))
      (node (ref "U1") (pin "34") (pinfunction "GND_34") (pintype "passive"))
      (node (ref "U2") (pin "107") (pinfunction "VSS_107") (pintype "passive"))
      (node (ref "U2") (pin "120") (pinfunction "VSS_120") (pintype "passive"))
      (node (ref "U2") (pin "130") (pinfunction "VSS_130") (pintype "passive"))
      (node (ref "U2") (pin "143") (pinfunction "VSS_143") (pintype "passive"))
      (node (ref "U2") (pin "16") (pinfunction "VSS_16") (pintype "passive"))
      (node (ref "U2") (pin "30") (pinfunction "VSSA_30") (pintype "passive"))
      (node (ref "U2") (pin "31") (pinfunction "Vref-_31") (pintype "passive"))
      (node (ref "U2") (pin "38") (pinfunction "VSS_38") (pintype "passive"))
      (node (ref "U2") (pin "51") (pinfunction "VSS_51") (pintype "passive"))
      (node (ref "U2") (pin "61") (pinfunction "VSS_61") (pintype "passive"))
      (node (ref "U2") (pin "71") (pinfunction "VSS_71") (pintype "passive"))
      (node (ref "U2") (pin "83") (pinfunction "VSS_83") (pintype "passive"))
      (node (ref "U2") (pin "94") (pinfunction "VSS_94") (pintype "passive"))
    )
    (net (code "119") (name "Net-(2.4'/2.8'LCD-BL_VDD)") (class "Default")
      (node (ref "2.4'/2.8'LCD") (pin "28") (pinfunction "BL_VDD_28") (pintype "passive"))
      (node (ref "C4") (pin "1") (pintype "passive"))
    )
    (net (code "120") (name "Net-(BOOT-Pad3)") (class "Default")
      (node (ref "BOOT") (pin "3") (pinfunction "3_3") (pintype "passive"))
      (node (ref "R11") (pin "1") (pintype "passive"))
    )
    (net (code "121") (name "Net-(BOOT-Pad4)") (class "Default")
      (node (ref "BOOT") (pin "4") (pinfunction "4_4") (pintype "passive"))
      (node (ref "R12") (pin "2") (pintype "passive"))
    )
    (net (code "122") (name "Net-(U2-OSC_IN)") (class "Default")
      (node (ref "C9") (pin "1") (pintype "passive"))
      (node (ref "R2") (pin "2") (pintype "passive"))
      (node (ref "U2") (pin "23") (pinfunction "OSC_IN_23") (pintype "passive"))
      (node (ref "Y2") (pin "1") (pinfunction "OSC1_1") (pintype "passive"))
    )
    (net (code "123") (name "Net-(U2-OSC_OUT)") (class "Default")
      (node (ref "C8") (pin "2") (pintype "passive"))
      (node (ref "R2") (pin "1") (pintype "passive"))
      (node (ref "U2") (pin "24") (pinfunction "OSC_OUT_24") (pintype "passive"))
      (node (ref "Y2") (pin "2") (pinfunction "OSC2_2") (pintype "passive"))
    )
    (net (code "124") (name "Net-(U2-PC14-OSC32_IN)") (class "Default")
      (node (ref "C5") (pin "2") (pintype "passive"))
      (node (ref "U2") (pin "8") (pinfunction "PC14-OSC32_IN_8") (pintype "passive"))
      (node (ref "Y1") (pin "2") (pinfunction "OSC2_2") (pintype "passive"))
    )
    (net (code "125") (name "Net-(U2-PC15-OSC32_OUT)") (class "Default")
      (node (ref "C6") (pin "2") (pintype "passive"))
      (node (ref "U2") (pin "9") (pinfunction "PC15-OSC32_OUT_9") (pintype "passive"))
      (node (ref "Y1") (pin "1") (pinfunction "OSC1_1") (pintype "passive"))
    )
    (net (code "126") (name "Net-(U2-VBAT)") (class "Default")
      (node (ref "C7") (pin "2") (pintype "passive"))
      (node (ref "D1") (pin "2") (pintype "passive"))
      (node (ref "D2") (pin "2") (pintype "passive"))
      (node (ref "U2") (pin "6") (pinfunction "VBAT_6") (pintype "passive"))
    )
    (net (code "127") (name "Net-(U2-VDDA)") (class "Default")
      (node (ref "C10") (pin "2") (pintype "passive"))
      (node (ref "C11") (pin "1") (pintype "passive"))
      (node (ref "R4") (pin "1") (pintype "passive"))
      (node (ref "U2") (pin "33") (pinfunction "VDDA_33") (pintype "passive"))
    )
    (net (code "128") (name "VCC3.3") (class "Default")
      (node (ref "2.4'/2.8'LCD") (pin "24") (pinfunction "VDD3.3_24") (pintype "passive"))
      (node (ref "2.4'/2.8'LCD") (pin "25") (pinfunction "VDD3.3_25") (pintype "passive"))
      (node (ref "BAT") (pin "1") (pinfunction "VCC_1") (pintype "passive"))
      (node (ref "BOOT") (pin "1") (pinfunction "1_1") (pintype "passive"))
      (node (ref "BOOT") (pin "2") (pinfunction "2_2") (pintype "passive"))
      (node (ref "C3") (pin "2") (pintype "passive"))
      (node (ref "D1") (pin "1") (pintype "passive"))
      (node (ref "D2") (pin "1") (pintype "passive"))
      (node (ref "JTAG") (pin "1") (pinfunction "VDD_1") (pintype "passive"))
      (node (ref "JTAG") (pin "2") (pinfunction "VDD_2") (pintype "passive"))
      (node (ref "R10") (pin "1") (pintype "passive"))
      (node (ref "R3") (pin "2") (pintype "passive"))
      (node (ref "R4") (pin "2") (pintype "passive"))
      (node (ref "R5") (pin "1") (pintype "passive"))
      (node (ref "R6") (pin "1") (pintype "passive"))
      (node (ref "R7") (pin "1") (pintype "passive"))
      (node (ref "R8") (pin "1") (pintype "passive"))
      (node (ref "R9") (pin "1") (pintype "passive"))
    )
    (net (code "129") (name "VCC3.3M") (class "Default")
      (node (ref "C1") (pin "2") (pintype "passive"))
      (node (ref "C13") (pin "2") (pintype "passive"))
      (node (ref "C14") (pin "2") (pintype "passive"))
      (node (ref "C15") (pin "2") (pintype "passive"))
      (node (ref "C16") (pin "2") (pintype "passive"))
      (node (ref "C17") (pin "2") (pintype "passive"))
      (node (ref "C18") (pin "2") (pintype "passive"))
      (node (ref "C19") (pin "2") (pintype "passive"))
      (node (ref "C2") (pin "1") (pintype "passive"))
      (node (ref "C20") (pin "2") (pintype "passive"))
      (node (ref "C21") (pin "2") (pintype "passive"))
      (node (ref "C22") (pin "2") (pintype "passive"))
      (node (ref "C23") (pin "2") (pintype "passive"))
      (node (ref "R1") (pin "2") (pintype "passive"))
      (node (ref "R8") (pin "2") (pintype "passive"))
      (node (ref "R9") (pin "2") (pintype "passive"))
      (node (ref "U1") (pin "11") (pinfunction "VDD_11") (pintype "passive"))
      (node (ref "U1") (pin "33") (pinfunction "VDD_33") (pintype "passive"))
      (node (ref "U2") (pin "108") (pinfunction "VDD_108") (pintype "passive"))
      (node (ref "U2") (pin "121") (pinfunction "VDD_121") (pintype "passive"))
      (node (ref "U2") (pin "131") (pinfunction "VDD_131") (pintype "passive"))
      (node (ref "U2") (pin "144") (pinfunction "VDD_144") (pintype "passive"))
      (node (ref "U2") (pin "17") (pinfunction "VDD_17") (pintype "passive"))
      (node (ref "U2") (pin "39") (pinfunction "VDD_39") (pintype "passive"))
      (node (ref "U2") (pin "52") (pinfunction "VDD_52") (pintype "passive"))
      (node (ref "U2") (pin "62") (pinfunction "VDD_62") (pintype "passive"))
      (node (ref "U2") (pin "72") (pinfunction "VDD_72") (pintype "passive"))
      (node (ref "U2") (pin "84") (pinfunction "VDD_84") (pintype "passive"))
      (node (ref "U2") (pin "95") (pinfunction "VDD_95") (pintype "passive"))
    )
    (net (code "130") (name "unconnected-(2.4'/2.8'LCD-MO-Pad32)") (class "Default")
      (node (ref "2.4'/2.8'LCD") (pin "32") (pinfunction "MO_32") (pintype "passive"))
    )
    (net (code "131") (name "unconnected-(JTAG-NC-Pad11)") (class "Default")
      (node (ref "JTAG") (pin "11") (pinfunction "NC_11") (pintype "passive"))
    )
    (net (code "132") (name "unconnected-(JTAG-NC-Pad17)") (class "Default")
      (node (ref "JTAG") (pin "17") (pinfunction "NC_17") (pintype "passive"))
    )
    (net (code "133") (name "unconnected-(JTAG-NC-Pad19)") (class "Default")
      (node (ref "JTAG") (pin "19") (pinfunction "NC_19") (pintype "passive"))
    )
    (net (code "134") (name "unconnected-(U1-I{slash}O3-Pad10)") (class "Default")
      (node (ref "U1") (pin "10") (pinfunction "I/O3_10") (pintype "passive"))
    )
    (net (code "135") (name "unconnected-(U1-I{slash}O6-Pad15)") (class "Default")
      (node (ref "U1") (pin "15") (pinfunction "I/O6_15") (pintype "passive"))
    )
    (net (code "136") (name "unconnected-(U1-I{slash}O9-Pad30)") (class "Default")
      (node (ref "U1") (pin "30") (pinfunction "I/O9_30") (pintype "passive"))
    )
    (net (code "137") (name "unconnected-(U1-I{slash}O12-Pad35)") (class "Default")
      (node (ref "U1") (pin "35") (pinfunction "I/O12_35") (pintype "passive"))
    )
    (net (code "138") (name "unconnected-(U1-I{slash}O15-Pad38)") (class "Default")
      (node (ref "U1") (pin "38") (pinfunction "I/O15_38") (pintype "passive"))
    )
    (net (code "139") (name "unconnected-(U2-NC-Pad106)") (class "Default")
      (node (ref "U2") (pin "106") (pinfunction "NC_106") (pintype "passive"))
    )
    (net (code "140") (name "unconnected-(U2-PA13{slash}JTMS_SWDIO-Pad105)") (class "Default")
      (node (ref "U2") (pin "105") (pinfunction "PA13/JTMS_SWDIO_105") (pintype "passive"))
    )
  )
)
